# WifiTracker.net
KiCad netlist of a schematic drawn in EAGLE
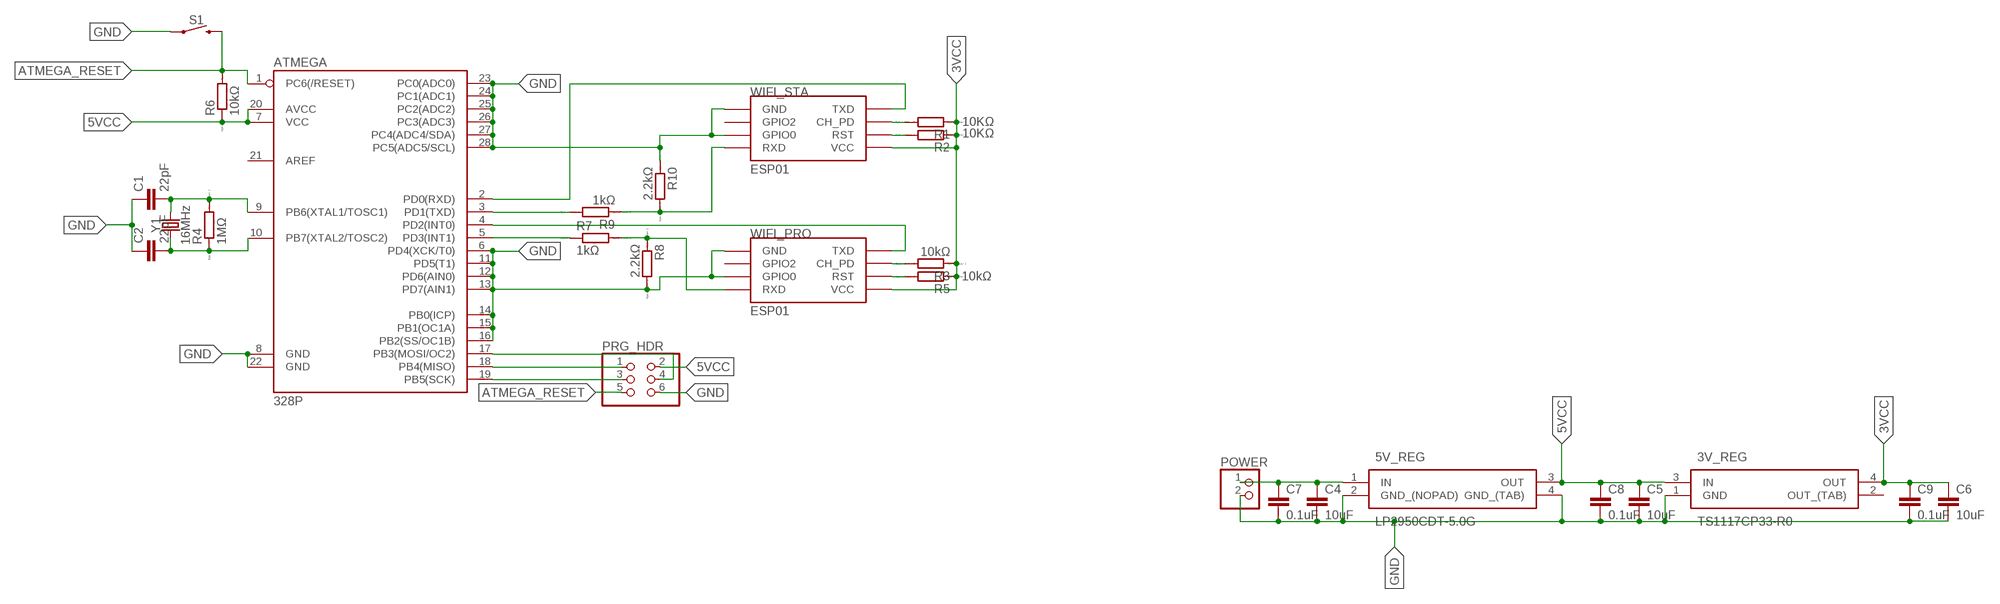
[diagram p0: schematic, sheet 1]

(export (version "E")
  (design (tool "Eeschema 10.0.6"))
  (components
    (comp (ref "3V_REG")
      (value "TS1117CP33-R0")
      (footprint "eagle-import:TO229P990X238-4N")
      (fields
        (field (name "MANUFACTURER_PART_NUMBER") "LP2950CDT-5.0G")
        (field (name "MOUSER_PART_NUMBER") "863-LP2950CDT-5.0G")
        (field (name "RS_PART_NUMBER") "0463593P")
      )
      (libsource (lib "eagle-import") (part "TS1117CP33-R0"))
    )
    (comp (ref "5V_REG")
      (value "LP2950CDT-5.0G")
      (footprint "eagle-import:TO229P990X238-4N")
      (fields
        (field (name "MOUSER_PART_NUMBER") "863-LP2950CDT-5.0G")
        (field (name "RS_PART_NUMBER") "0463593P")
      )
      (libsource (lib "eagle-import") (part "LP2950CDT-5.0G"))
    )
    (comp (ref "ATMEGA")
      (value "328P")
      (footprint "eagle-import:DIP28")
      (libsource (lib "eagle-import") (part "ATMEGA328P_PDIP"))
    )
    (comp (ref "C1")
      (value "22pF")
      (footprint "eagle-import:1206")
      (libsource (lib "eagle-import") (part "1.0UF-1206-50V-10%"))
    )
    (comp (ref "C2")
      (value "22pF")
      (footprint "eagle-import:1206")
      (libsource (lib "eagle-import") (part "1.0UF-1206-50V-10%"))
    )
    (comp (ref "C4")
      (value "10uF")
      (footprint "eagle-import:1206")
      (libsource (lib "eagle-import") (part "1.0UF-1206-50V-10%"))
    )
    (comp (ref "C5")
      (value "10uF")
      (footprint "eagle-import:1206")
      (libsource (lib "eagle-import") (part "1.0UF-1206-50V-10%"))
    )
    (comp (ref "C6")
      (value "10uF")
      (footprint "eagle-import:1206")
      (libsource (lib "eagle-import") (part "1.0UF-1206-50V-10%"))
    )
    (comp (ref "C7")
      (value "0.1uF")
      (footprint "eagle-import:1206")
      (libsource (lib "eagle-import") (part "1.0UF-1206-50V-10%"))
    )
    (comp (ref "C8")
      (value "0.1uF")
      (footprint "eagle-import:1206")
      (libsource (lib "eagle-import") (part "1.0UF-1206-50V-10%"))
    )
    (comp (ref "C9")
      (value "0.1uF")
      (footprint "eagle-import:1206")
      (libsource (lib "eagle-import") (part "1.0UF-1206-50V-10%"))
    )
    (comp (ref "POWER")
      (value "PINHD-1X2")
      (footprint "eagle-import:1X02")
      (libsource (lib "eagle-import") (part "PINHD-1X2"))
    )
    (comp (ref "PRG_HDR")
      (value "PINHD-2X3")
      (footprint "eagle-import:2X03")
      (libsource (lib "eagle-import") (part "PINHD-2X3"))
    )
    (comp (ref "R1")
      (value "10KΩ")
      (footprint "eagle-import:R1210")
      (libsource (lib "eagle-import") (part "RR1210"))
    )
    (comp (ref "R2")
      (value "10KΩ")
      (footprint "eagle-import:R1210")
      (libsource (lib "eagle-import") (part "RR1210"))
    )
    (comp (ref "R3")
      (value "10kΩ")
      (footprint "eagle-import:R1210")
      (libsource (lib "eagle-import") (part "RR1210"))
    )
    (comp (ref "R4")
      (value "1MΩ")
      (footprint "eagle-import:R1210")
      (libsource (lib "eagle-import") (part "RR1210"))
    )
    (comp (ref "R5")
      (value "10kΩ")
      (footprint "eagle-import:R1210")
      (libsource (lib "eagle-import") (part "RR1210"))
    )
    (comp (ref "R6")
      (value "10kΩ")
      (footprint "eagle-import:R1210")
      (libsource (lib "eagle-import") (part "RR1210"))
    )
    (comp (ref "R7")
      (value "1kΩ")
      (footprint "eagle-import:R1210")
      (libsource (lib "eagle-import") (part "RR1210"))
    )
    (comp (ref "R8")
      (value "2.2kΩ")
      (footprint "eagle-import:R1210")
      (libsource (lib "eagle-import") (part "RR1210"))
    )
    (comp (ref "R9")
      (value "1kΩ")
      (footprint "eagle-import:R1210")
      (libsource (lib "eagle-import") (part "RR1210"))
    )
    (comp (ref "R10")
      (value "2.2kΩ")
      (footprint "eagle-import:R1210")
      (libsource (lib "eagle-import") (part "RR1210"))
    )
    (comp (ref "S1")
      (value "MOMENTARY-SWITCH-SPST-PTH-6.0MM")
      (footprint "eagle-import:TACTILE_SWITCH_PTH_6.0MM")
      (libsource (lib "eagle-import") (part "MOMENTARY-SWITCH-SPST-PTH-6.0MM"))
    )
    (comp (ref "WIFI_PRO")
      (value "ESP01")
      (footprint "eagle-import:ESP01")
      (libsource (lib "eagle-import") (part "ESP01"))
    )
    (comp (ref "WIFI_STA")
      (value "ESP01")
      (footprint "eagle-import:ESP01")
      (libsource (lib "eagle-import") (part "ESP01"))
    )
    (comp (ref "Y1")
      (value "16MHz")
      (footprint "eagle-import:HC49UP")
      (libsource (lib "eagle-import") (part "CRYSTAL-8MHZSMD-HC49UP"))
    )
  )
  (nets
    (net (code "1") (name "3VCC") (class "Default")
      (node (ref "3V_REG") (pin "4") (pinfunction "OUT_4") (pintype "output"))
      (node (ref "C6") (pin "1") (pinfunction "1_1") (pintype "passive"))
      (node (ref "C9") (pin "1") (pinfunction "1_1") (pintype "passive"))
      (node (ref "R1") (pin "1") (pinfunction "1_1") (pintype "passive"))
      (node (ref "R2") (pin "1") (pinfunction "1_1") (pintype "passive"))
      (node (ref "R3") (pin "1") (pinfunction "1_1") (pintype "passive"))
      (node (ref "R5") (pin "1") (pinfunction "1_1") (pintype "passive"))
      (node (ref "WIFI_PRO") (pin "VCC") (pinfunction "VCC_VCC") (pintype "bidirectional"))
      (node (ref "WIFI_STA") (pin "VCC") (pinfunction "VCC_VCC") (pintype "bidirectional"))
    )
    (net (code "2") (name "5VCC") (class "Default")
      (node (ref "3V_REG") (pin "3") (pinfunction "IN_3") (pintype "input"))
      (node (ref "5V_REG") (pin "3") (pinfunction "OUT_3") (pintype "output"))
      (node (ref "ATMEGA") (pin "20") (pinfunction "AVCC_20") (pintype "bidirectional"))
      (node (ref "ATMEGA") (pin "7") (pinfunction "VCC_7") (pintype "bidirectional"))
      (node (ref "C5") (pin "1") (pinfunction "1_1") (pintype "passive"))
      (node (ref "C8") (pin "1") (pinfunction "1_1") (pintype "passive"))
      (node (ref "PRG_HDR") (pin "2") (pinfunction "2_2") (pintype "passive"))
      (node (ref "R6") (pin "1") (pinfunction "1_1") (pintype "passive"))
    )
    (net (code "3") (name "ATMEGA_RESET") (class "Default")
      (node (ref "ATMEGA") (pin "1") (pinfunction "PC6(/RESET)_1") (pintype "bidirectional"))
      (node (ref "PRG_HDR") (pin "5") (pinfunction "5_5") (pintype "passive"))
      (node (ref "R6") (pin "2") (pinfunction "2_2") (pintype "passive"))
      (node (ref "S1") (pin "3") (pinfunction "2_3") (pintype "passive"))
    )
    (net (code "4") (name "GND") (class "Default")
      (node (ref "3V_REG") (pin "1") (pinfunction "GND_1") (pintype "power_in"))
      (node (ref "5V_REG") (pin "2") (pinfunction "GND_(NOPAD)_2") (pintype "power_in"))
      (node (ref "5V_REG") (pin "4") (pinfunction "GND_(TAB)_4") (pintype "power_in"))
      (node (ref "ATMEGA") (pin "11") (pinfunction "PD5(T1)_11") (pintype "bidirectional"))
      (node (ref "ATMEGA") (pin "12") (pinfunction "PD6(AIN0)_12") (pintype "bidirectional"))
      (node (ref "ATMEGA") (pin "13") (pinfunction "PD7(AIN1)_13") (pintype "bidirectional"))
      (node (ref "ATMEGA") (pin "14") (pinfunction "PB0(ICP)_14") (pintype "bidirectional"))
      (node (ref "ATMEGA") (pin "15") (pinfunction "PB1(OC1A)_15") (pintype "bidirectional"))
      (node (ref "ATMEGA") (pin "16") (pinfunction "PB2(SS/OC1B)_16") (pintype "bidirectional"))
      (node (ref "ATMEGA") (pin "22") (pinfunction "GND_22") (pintype "bidirectional"))
      (node (ref "ATMEGA") (pin "23") (pinfunction "PC0(ADC0)_23") (pintype "bidirectional"))
      (node (ref "ATMEGA") (pin "24") (pinfunction "PC1(ADC1)_24") (pintype "bidirectional"))
      (node (ref "ATMEGA") (pin "25") (pinfunction "PC2(ADC2)_25") (pintype "bidirectional"))
      (node (ref "ATMEGA") (pin "26") (pinfunction "PC3(ADC3)_26") (pintype "bidirectional"))
      (node (ref "ATMEGA") (pin "27") (pinfunction "PC4(ADC4/SDA)_27") (pintype "bidirectional"))
      (node (ref "ATMEGA") (pin "28") (pinfunction "PC5(ADC5/SCL)_28") (pintype "bidirectional"))
      (node (ref "ATMEGA") (pin "6") (pinfunction "PD4(XCK/T0)_6") (pintype "bidirectional"))
      (node (ref "ATMEGA") (pin "8") (pinfunction "GND_8") (pintype "bidirectional"))
      (node (ref "C1") (pin "1") (pinfunction "1_1") (pintype "passive"))
      (node (ref "C2") (pin "1") (pinfunction "1_1") (pintype "passive"))
      (node (ref "C4") (pin "2") (pinfunction "2_2") (pintype "passive"))
      (node (ref "C5") (pin "2") (pinfunction "2_2") (pintype "passive"))
      (node (ref "C6") (pin "2") (pinfunction "2_2") (pintype "passive"))
      (node (ref "C7") (pin "2") (pinfunction "2_2") (pintype "passive"))
      (node (ref "C8") (pin "2") (pinfunction "2_2") (pintype "passive"))
      (node (ref "C9") (pin "2") (pinfunction "2_2") (pintype "passive"))
      (node (ref "POWER") (pin "2") (pinfunction "2_2") (pintype "passive"))
      (node (ref "PRG_HDR") (pin "6") (pinfunction "6_6") (pintype "passive"))
      (node (ref "R10") (pin "1") (pinfunction "1_1") (pintype "passive"))
      (node (ref "R8") (pin "2") (pinfunction "2_2") (pintype "passive"))
      (node (ref "S1") (pin "1") (pinfunction "1_1") (pintype "passive"))
      (node (ref "WIFI_PRO") (pin "GND") (pinfunction "GND_GND") (pintype "bidirectional"))
      (node (ref "WIFI_PRO") (pin "GPIO0") (pinfunction "GPIO0_GPIO0") (pintype "bidirectional"))
      (node (ref "WIFI_STA") (pin "GND") (pinfunction "GND_GND") (pintype "bidirectional"))
      (node (ref "WIFI_STA") (pin "GPIO0") (pinfunction "GPIO0_GPIO0") (pintype "bidirectional"))
    )
    (net (code "5") (name "Net-(5V_REG-IN)") (class "Default")
      (node (ref "5V_REG") (pin "1") (pinfunction "IN_1") (pintype "input"))
      (node (ref "C4") (pin "1") (pinfunction "1_1") (pintype "passive"))
      (node (ref "C7") (pin "1") (pinfunction "1_1") (pintype "passive"))
      (node (ref "POWER") (pin "1") (pinfunction "1_1") (pintype "passive"))
    )
    (net (code "6") (name "Net-(ATMEGA-PB3(MOSI{slash}OC2))") (class "Default")
      (node (ref "ATMEGA") (pin "17") (pinfunction "PB3(MOSI/OC2)_17") (pintype "bidirectional"))
      (node (ref "PRG_HDR") (pin "4") (pinfunction "4_4") (pintype "passive"))
    )
    (net (code "7") (name "Net-(ATMEGA-PB4(MISO))") (class "Default")
      (node (ref "ATMEGA") (pin "18") (pinfunction "PB4(MISO)_18") (pintype "bidirectional"))
      (node (ref "PRG_HDR") (pin "1") (pinfunction "1_1") (pintype "passive"))
    )
    (net (code "8") (name "Net-(ATMEGA-PB5(SCK))") (class "Default")
      (node (ref "ATMEGA") (pin "19") (pinfunction "PB5(SCK)_19") (pintype "bidirectional"))
      (node (ref "PRG_HDR") (pin "3") (pinfunction "3_3") (pintype "passive"))
    )
    (net (code "9") (name "Net-(ATMEGA-PB6(XTAL1{slash}TOSC1))") (class "Default")
      (node (ref "ATMEGA") (pin "9") (pinfunction "PB6(XTAL1/TOSC1)_9") (pintype "bidirectional"))
      (node (ref "C1") (pin "2") (pinfunction "2_2") (pintype "passive"))
      (node (ref "R4") (pin "2") (pinfunction "2_2") (pintype "passive"))
      (node (ref "Y1") (pin "2") (pinfunction "2_2") (pintype "passive"))
    )
    (net (code "10") (name "Net-(ATMEGA-PB7(XTAL2{slash}TOSC2))") (class "Default")
      (node (ref "ATMEGA") (pin "10") (pinfunction "PB7(XTAL2/TOSC2)_10") (pintype "bidirectional"))
      (node (ref "C2") (pin "2") (pinfunction "2_2") (pintype "passive"))
      (node (ref "R4") (pin "1") (pinfunction "1_1") (pintype "passive"))
      (node (ref "Y1") (pin "1") (pinfunction "1_1") (pintype "passive"))
    )
    (net (code "11") (name "Net-(ATMEGA-PD0(RXD))") (class "Default")
      (node (ref "ATMEGA") (pin "2") (pinfunction "PD0(RXD)_2") (pintype "bidirectional"))
      (node (ref "WIFI_STA") (pin "TX") (pinfunction "TXD_TX") (pintype "bidirectional"))
    )
    (net (code "12") (name "Net-(ATMEGA-PD1(TXD))") (class "Default")
      (node (ref "ATMEGA") (pin "3") (pinfunction "PD1(TXD)_3") (pintype "bidirectional"))
      (node (ref "R9") (pin "2") (pinfunction "2_2") (pintype "passive"))
    )
    (net (code "13") (name "Net-(ATMEGA-PD2(INT0))") (class "Default")
      (node (ref "ATMEGA") (pin "4") (pinfunction "PD2(INT0)_4") (pintype "bidirectional"))
      (node (ref "WIFI_PRO") (pin "TX") (pinfunction "TXD_TX") (pintype "bidirectional"))
    )
    (net (code "14") (name "Net-(ATMEGA-PD3(INT1))") (class "Default")
      (node (ref "ATMEGA") (pin "5") (pinfunction "PD3(INT1)_5") (pintype "bidirectional"))
      (node (ref "R7") (pin "1") (pinfunction "1_1") (pintype "passive"))
    )
    (net (code "15") (name "Net-(R1-Pad2)") (class "Default")
      (node (ref "R1") (pin "2") (pinfunction "2_2") (pintype "passive"))
      (node (ref "WIFI_STA") (pin "CH_PD") (pinfunction "CH_PD_CH_PD") (pintype "bidirectional"))
    )
    (net (code "16") (name "Net-(R2-Pad2)") (class "Default")
      (node (ref "R2") (pin "2") (pinfunction "2_2") (pintype "passive"))
      (node (ref "WIFI_STA") (pin "RST") (pinfunction "RST_RST") (pintype "bidirectional"))
    )
    (net (code "17") (name "Net-(R3-Pad2)") (class "Default")
      (node (ref "R3") (pin "2") (pinfunction "2_2") (pintype "passive"))
      (node (ref "WIFI_PRO") (pin "CH_PD") (pinfunction "CH_PD_CH_PD") (pintype "bidirectional"))
    )
    (net (code "18") (name "Net-(R5-Pad2)") (class "Default")
      (node (ref "R5") (pin "2") (pinfunction "2_2") (pintype "passive"))
      (node (ref "WIFI_PRO") (pin "RST") (pinfunction "RST_RST") (pintype "bidirectional"))
    )
    (net (code "19") (name "Net-(WIFI_PRO-RXD)") (class "Default")
      (node (ref "R7") (pin "2") (pinfunction "2_2") (pintype "passive"))
      (node (ref "R8") (pin "1") (pinfunction "1_1") (pintype "passive"))
      (node (ref "WIFI_PRO") (pin "RX") (pinfunction "RXD_RX") (pintype "bidirectional"))
    )
    (net (code "20") (name "Net-(WIFI_STA-RXD)") (class "Default")
      (node (ref "R10") (pin "2") (pinfunction "2_2") (pintype "passive"))
      (node (ref "R9") (pin "1") (pinfunction "1_1") (pintype "passive"))
      (node (ref "WIFI_STA") (pin "RX") (pinfunction "RXD_RX") (pintype "bidirectional"))
    )
    (net (code "21") (name "unconnected-(3V_REG-OUT_(TAB)-Pad2)") (class "Default")
      (node (ref "3V_REG") (pin "2") (pinfunction "OUT_(TAB)_2") (pintype "output"))
    )
    (net (code "22") (name "unconnected-(ATMEGA-AREF-Pad21)") (class "Default")
      (node (ref "ATMEGA") (pin "21") (pinfunction "AREF_21") (pintype "bidirectional"))
    )
    (net (code "23") (name "unconnected-(WIFI_PRO-PadGPIO2)") (class "Default")
      (node (ref "WIFI_PRO") (pin "GPIO2") (pinfunction "GPIO2_GPIO2") (pintype "bidirectional"))
    )
    (net (code "24") (name "unconnected-(WIFI_STA-PadGPIO2)") (class "Default")
      (node (ref "WIFI_STA") (pin "GPIO2") (pinfunction "GPIO2_GPIO2") (pintype "bidirectional"))
    )
  )
)
